# SH3_-_SENSORS.net
KiCad netlist of a schematic drawn in Altium Designer
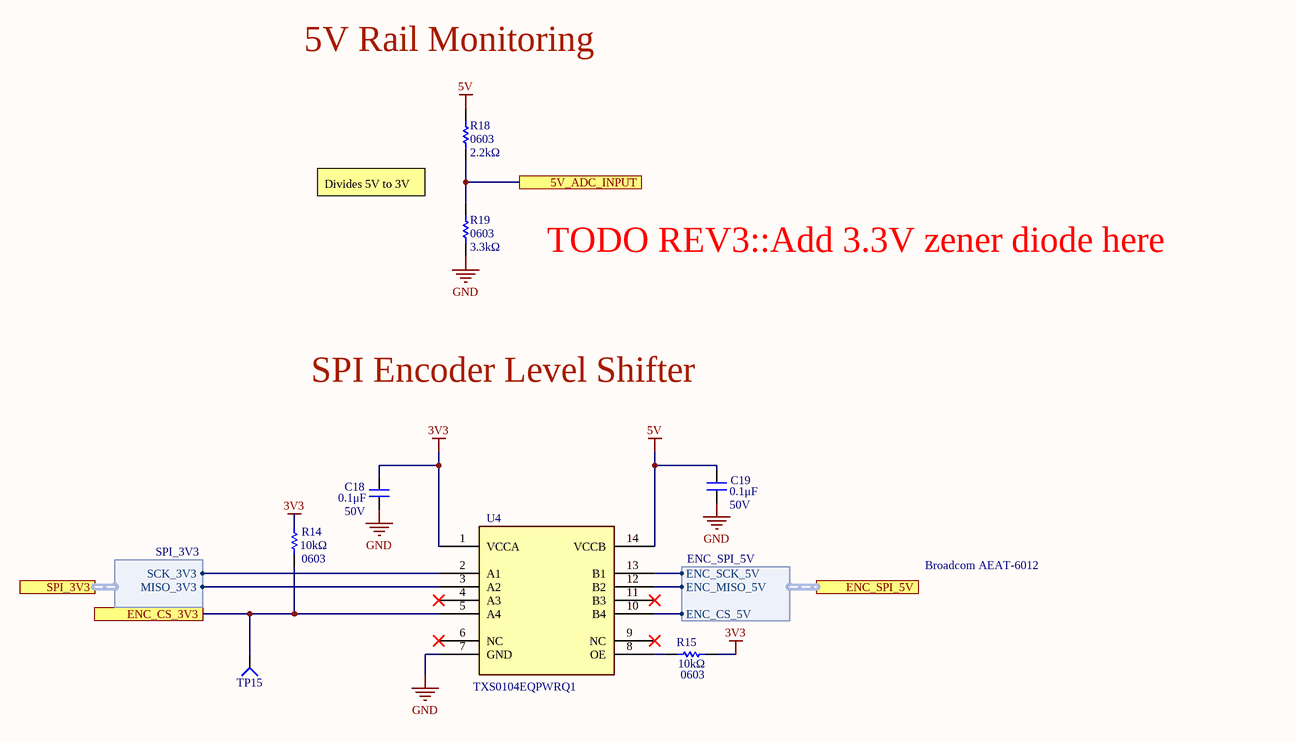
[diagram p0: SH3 - SENSORS.SchDoc]

(export (version "E")
  (design (tool "Eeschema 10.0.6"))
  (components
    (comp (ref "C18")
      (value "0.1μF")
      (footprint "CAP0603")
      (description "CAP CER 0.1UF 50V X7R 0603")
      (fields (field (name "VOLTAGE RATING") "50V") (field (name "Comment") "CAP_0.1uF_50V_0603"))
      (libsource (lib "UWRT_Schematic_Library_2020") (part "CAP_0.1uF_50V_0603"))
    )
    (comp (ref "C19")
      (value "0.1μF")
      (footprint "CAP0603")
      (description "CAP CER 0.1UF 50V X7R 0603")
      (fields (field (name "VOLTAGE RATING") "50V") (field (name "Comment") "CAP_0.1uF_50V_0603"))
      (libsource (lib "UWRT_Schematic_Library_2020") (part "CAP_0.1uF_50V_0603"))
    )
    (comp (ref "R14")
      (value "10kΩ")
      (footprint "RESC0603(1608)_N")
      (description "RES 10K OHM 5% 1/10W 0603")
      (fields
        (field (name "TOLERANCE") "5%")
        (field (name "CASE CODE (IMPERIAL)") "0603")
        (field (name "Comment") "RES_10kΩ_0603")
      )
      (libsource (lib "UWRT_Schematic_Library_2020") (part "RES_10kΩ_0603_5%"))
    )
    (comp (ref "R15")
      (value "10kΩ")
      (footprint "RESC0603(1608)_N")
      (description "RES 10K OHM 5% 1/10W 0603")
      (fields
        (field (name "TOLERANCE") "5%")
        (field (name "CASE CODE (IMPERIAL)") "0603")
        (field (name "Comment") "RES_10kΩ_0603")
      )
      (libsource (lib "UWRT_Schematic_Library_2020") (part "RES_10kΩ_0603_5%"))
    )
    (comp (ref "R18")
      (value "2.2kΩ")
      (footprint "RESC0603(1608)_N")
      (description "RES 2.2K OHM 1% 1/10W 0603")
      (fields
        (field (name "TOLERANCE") "1%")
        (field (name "CASE CODE (IMPERIAL)") "0603")
        (field (name "Comment") "RES_2.2kΩ_0603")
      )
      (libsource (lib "UWRT_Schematic_Library_2020") (part "RES_2.2kΩ_0603_1%"))
    )
    (comp (ref "R19")
      (value "3.3kΩ")
      (footprint "RESC0603(1608)_N")
      (description "RES 3.3K OHM 5% 1/10W 0603")
      (fields
        (field (name "TOLERANCE") "5%")
        (field (name "CASE CODE (IMPERIAL)") "0603")
        (field (name "Comment") "RES_3.3kΩ_0603")
      )
      (libsource (lib "UWRT_Schematic_Library_2020") (part "RES_3.3kΩ_0603_5%"))
    )
    (comp (ref "TP15")
      (value "TESTPOINT_1MM_CIRCLE")
      (footprint "TESTPOINT_CIRCLE_1MM")
      (description "TESTPOINT 1MM CIRCLE")
      (libsource (lib "UWRT_Schematic_Library_2020") (part "TESTPOINT_1MM_CIRCLE"))
    )
    (comp (ref "U4")
      (value "TXS0104EQPWRQ1")
      (footprint "UWRT_Footprint_Library_2020:TXS0104EQPWRQ1")
      (description "IC BIDIRECTIONAL LEVEL SHIFTER 4 CHANNEL 14TSSOP")
      (fields (field (name "MANUFACTURER") "Texas Instruments"))
      (libsource (lib "UWRT_Schematic_Library_2020") (part "IC_LVL_SHIFTER_4_CH"))
    )
  )
  (nets
    (net (code "3") (name "/5V_ADC_INPUT") (class "Default")
      (node (ref "R18") (pin "1") (pinfunction "1_1") (pintype "passive"))
      (node (ref "R19") (pin "2") (pinfunction "2_2") (pintype "passive"))
    )
    (net (code "4") (name "/ENC_CS_3V3") (class "Default")
      (node (ref "R14") (pin "1") (pinfunction "1_1") (pintype "passive"))
      (node (ref "TP15") (pin "1") (pinfunction "=value_1") (pintype "passive"))
      (node (ref "U4") (pin "5") (pinfunction "A4_5") (pintype "passive"))
    )
    (net (code "5") (name "/ENC_CS_5V") (class "Default")
      (node (ref "U4") (pin "10") (pinfunction "B4_10") (pintype "passive"))
    )
    (net (code "6") (name "/ENC_MISO_5V") (class "Default")
      (node (ref "U4") (pin "12") (pinfunction "B2_12") (pintype "passive"))
    )
    (net (code "7") (name "/ENC_SCK_5V") (class "Default")
      (node (ref "U4") (pin "13") (pinfunction "B1_13") (pintype "passive"))
    )
    (net (code "8") (name "/MISO_3V3") (class "Default")
      (node (ref "U4") (pin "3") (pinfunction "A2_3") (pintype "passive"))
    )
    (net (code "9") (name "/SCK_3V3") (class "Default")
      (node (ref "U4") (pin "2") (pinfunction "A1_2") (pintype "passive"))
    )
    (net (code "12") (name "3V3") (class "Default")
      (node (ref "C18") (pin "2") (pinfunction "2_2") (pintype "passive"))
      (node (ref "R14") (pin "2") (pinfunction "2_2") (pintype "passive"))
      (node (ref "R15") (pin "2") (pinfunction "2_2") (pintype "passive"))
      (node (ref "U4") (pin "1") (pinfunction "VCCA_1") (pintype "passive"))
    )
    (net (code "13") (name "5V") (class "Default")
      (node (ref "C19") (pin "2") (pinfunction "2_2") (pintype "passive"))
      (node (ref "R18") (pin "2") (pinfunction "2_2") (pintype "passive"))
      (node (ref "U4") (pin "14") (pinfunction "VCCB_14") (pintype "passive"))
    )
    (net (code "14") (name "GND") (class "Default")
      (node (ref "C18") (pin "1") (pinfunction "1_1") (pintype "passive"))
      (node (ref "C19") (pin "1") (pinfunction "1_1") (pintype "passive"))
      (node (ref "R19") (pin "1") (pinfunction "1_1") (pintype "passive"))
      (node (ref "U4") (pin "7") (pinfunction "GND_7") (pintype "passive"))
    )
    (net (code "15") (name "Net-(U4-OE)") (class "Default")
      (node (ref "R15") (pin "1") (pinfunction "1_1") (pintype "passive"))
      (node (ref "U4") (pin "8") (pinfunction "OE_8") (pintype "passive"))
    )
    (net (code "16") (name "unconnected-(U4-A3-Pad4)") (class "Default")
      (node (ref "U4") (pin "4") (pinfunction "A3_4") (pintype "passive+no_connect"))
    )
    (net (code "17") (name "unconnected-(U4-B3-Pad11)") (class "Default")
      (node (ref "U4") (pin "11") (pinfunction "B3_11") (pintype "passive+no_connect"))
    )
    (net (code "18") (name "unconnected-(U4-NC-Pad6)") (class "Default")
      (node (ref "U4") (pin "6") (pinfunction "NC_6") (pintype "passive+no_connect"))
    )
    (net (code "19") (name "unconnected-(U4-NC-Pad9)") (class "Default")
      (node (ref "U4") (pin "9") (pinfunction "NC_9") (pintype "passive+no_connect"))
    )
  )
)
